# COMM.net
KiCad netlist of a schematic drawn in Altium Designer
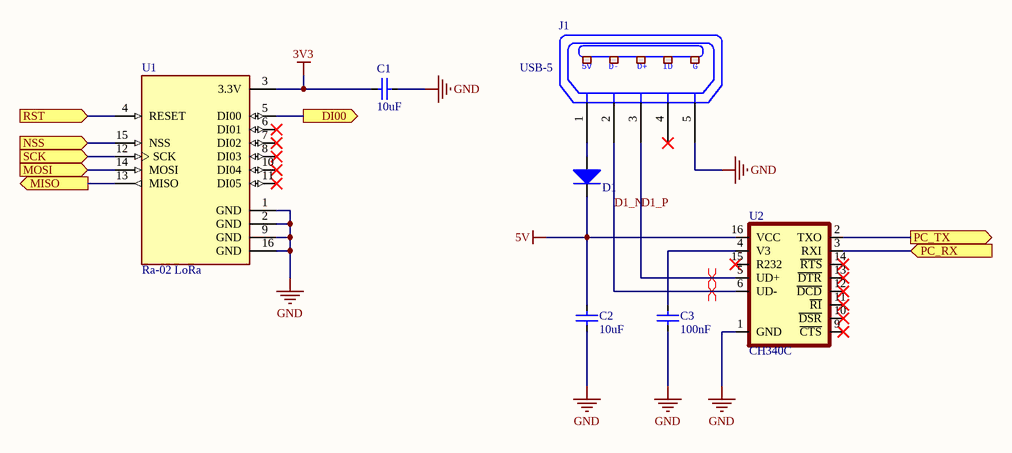
[diagram p0: COMM.SchDoc]

(export (version "E")
  (design (tool "Eeschema 10.0.6"))
  (components
    (comp (ref "C1")
      (value "10uF")
      (footprint "CAP_0805")
      (description "Capacitor")
      (fields (field (name "PUBLISHER") "Altium Limited"))
      (libsource (lib "My Library") (part "CapSMD"))
    )
    (comp (ref "C2")
      (value "10uF")
      (footprint "CAP_0805")
      (description "Capacitor")
      (fields (field (name "PUBLISHER") "Altium Limited"))
      (libsource (lib "My Library") (part "CapSMD"))
    )
    (comp (ref "C3")
      (value "100nF")
      (footprint "CAP_0805")
      (description "Capacitor")
      (fields (field (name "PUBLISHER") "Altium Limited"))
      (libsource (lib "My Library") (part "CapSMD"))
    )
    (comp (ref "D1")
      (value "Diode SMD")
      (footprint "DIO-214AC(SMA)")
      (description "Default Diode")
      (fields (field (name "PUBLISHER") "Altium Limited"))
      (libsource (lib "My Library") (part "Diode SMD"))
    )
    (comp (ref "J1")
      (value "USB-5")
      (footprint "USB-M1")
      (fields
        (field (name "MANUFACTURER") "FCI")
        (field (name "MANUFACTURER PART NUMBER") "10118193-0001LF")
        (field (name ".CREATOR") "MM")
        (field (name ".CHECKED PCB") "RF")
        (field (name ".CHECKED SCH") "MM")
      )
      (libsource (lib "My Library") (part "USB-5"))
    )
    (comp (ref "U1")
      (value "Ra-02 LoRa")
      (footprint "Ra-02")
      (description "LoRa Module Ra-02")
      (libsource (lib "My Library") (part "Ra-02 LoRa"))
    )
    (comp (ref "U2")
      (value "CH340C")
      (footprint "SOP-16")
      (description "USB to serial chip CH340")
      (fields (field (name "MF") "WCH"))
      (libsource (lib "My Library") (part "CH340C"))
    )
  )
  (nets
    (net (code "1") (name "/D1_N") (class "Default")
      (node (ref "J1") (pin "2") (pinfunction "P2_2") (pintype "passive"))
      (node (ref "U2") (pin "6") (pinfunction "UD-_6") (pintype "bidirectional"))
    )
    (net (code "2") (name "/D1_P") (class "Default")
      (node (ref "J1") (pin "3") (pinfunction "P3_3") (pintype "passive"))
      (node (ref "U2") (pin "5") (pinfunction "UD+_5") (pintype "bidirectional"))
    )
    (net (code "3") (name "/DI00") (class "Default")
      (node (ref "U1") (pin "5") (pinfunction "DI00_5") (pintype "bidirectional"))
    )
    (net (code "4") (name "/MISO") (class "Default")
      (node (ref "U1") (pin "13") (pinfunction "MISO_13") (pintype "output"))
    )
    (net (code "5") (name "/MOSI") (class "Default")
      (node (ref "U1") (pin "14") (pinfunction "MOSI_14") (pintype "input"))
    )
    (net (code "6") (name "/NSS") (class "Default")
      (node (ref "U1") (pin "15") (pinfunction "NSS_15") (pintype "input"))
    )
    (net (code "7") (name "/PC_RX") (class "Default")
      (node (ref "U2") (pin "3") (pinfunction "RXI_3") (pintype "bidirectional"))
    )
    (net (code "8") (name "/PC_TX") (class "Default")
      (node (ref "U2") (pin "2") (pinfunction "TXO_2") (pintype "bidirectional"))
    )
    (net (code "9") (name "/RST") (class "Default")
      (node (ref "U1") (pin "4") (pinfunction "RESET_4") (pintype "input"))
    )
    (net (code "10") (name "/SCK") (class "Default")
      (node (ref "U1") (pin "12") (pinfunction "SCK_12") (pintype "input"))
    )
    (net (code "11") (name "3V3") (class "Default")
      (node (ref "C1") (pin "2") (pinfunction "2_2") (pintype "passive"))
      (node (ref "U1") (pin "3") (pinfunction "3.3V_3") (pintype "power_in"))
    )
    (net (code "12") (name "5V") (class "Default")
      (node (ref "C2") (pin "2") (pinfunction "2_2") (pintype "passive"))
      (node (ref "D1") (pin "2") (pinfunction "K_2") (pintype "passive"))
      (node (ref "U2") (pin "16") (pinfunction "VCC_16") (pintype "bidirectional"))
    )
    (net (code "13") (name "GND") (class "Default")
      (node (ref "C1") (pin "1") (pinfunction "1_1") (pintype "passive"))
      (node (ref "C2") (pin "1") (pinfunction "1_1") (pintype "passive"))
      (node (ref "C3") (pin "1") (pinfunction "1_1") (pintype "passive"))
      (node (ref "J1") (pin "5") (pinfunction "P5_5") (pintype "passive"))
      (node (ref "U1") (pin "1") (pinfunction "GND_1") (pintype "power_in"))
      (node (ref "U1") (pin "16") (pinfunction "GND_16") (pintype "power_in"))
      (node (ref "U1") (pin "2") (pinfunction "GND_2") (pintype "power_in"))
      (node (ref "U1") (pin "9") (pinfunction "GND_9") (pintype "power_in"))
      (node (ref "U2") (pin "1") (pinfunction "GND_1") (pintype "bidirectional"))
    )
    (net (code "14") (name "Net-(D1-A)") (class "Default")
      (node (ref "D1") (pin "1") (pinfunction "A_1") (pintype "passive"))
      (node (ref "J1") (pin "1") (pinfunction "P1_1") (pintype "passive"))
    )
    (net (code "15") (name "Net-(U2-V3)") (class "Default")
      (node (ref "C3") (pin "2") (pinfunction "2_2") (pintype "passive"))
      (node (ref "U2") (pin "4") (pinfunction "V3_4") (pintype "bidirectional"))
    )
    (net (code "16") (name "unconnected-(J1-P4-Pad4)") (class "Default")
      (node (ref "J1") (pin "4") (pinfunction "P4_4") (pintype "passive+no_connect"))
    )
    (net (code "17") (name "unconnected-(U1-DI01-Pad6)") (class "Default")
      (node (ref "U1") (pin "6") (pinfunction "DI01_6") (pintype "bidirectional+no_connect"))
    )
    (net (code "18") (name "unconnected-(U1-DI02-Pad7)") (class "Default")
      (node (ref "U1") (pin "7") (pinfunction "DI02_7") (pintype "bidirectional+no_connect"))
    )
    (net (code "19") (name "unconnected-(U1-DI03-Pad8)") (class "Default")
      (node (ref "U1") (pin "8") (pinfunction "DI03_8") (pintype "bidirectional+no_connect"))
    )
    (net (code "20") (name "unconnected-(U1-DI04-Pad10)") (class "Default")
      (node (ref "U1") (pin "10") (pinfunction "DI04_10") (pintype "bidirectional+no_connect"))
    )
    (net (code "21") (name "unconnected-(U1-DI05-Pad11)") (class "Default")
      (node (ref "U1") (pin "11") (pinfunction "DI05_11") (pintype "bidirectional+no_connect"))
    )
    (net (code "22") (name "unconnected-(U2-R232-Pad15)") (class "Default")
      (node (ref "U2") (pin "15") (pinfunction "R232_15") (pintype "bidirectional+no_connect"))
    )
    (net (code "23") (name "unconnected-(U2-~{CTS}-Pad9)") (class "Default")
      (node (ref "U2") (pin "9") (pinfunction "~{CTS}_9") (pintype "bidirectional+no_connect"))
    )
    (net (code "24") (name "unconnected-(U2-~{DCD}-Pad12)") (class "Default")
      (node (ref "U2") (pin "12") (pinfunction "~{DCD}_12") (pintype "bidirectional+no_connect"))
    )
    (net (code "25") (name "unconnected-(U2-~{DSR}-Pad10)") (class "Default")
      (node (ref "U2") (pin "10") (pinfunction "~{DSR}_10") (pintype "bidirectional+no_connect"))
    )
    (net (code "26") (name "unconnected-(U2-~{DTR}-Pad13)") (class "Default")
      (node (ref "U2") (pin "13") (pinfunction "~{DTR}_13") (pintype "bidirectional+no_connect"))
    )
    (net (code "27") (name "unconnected-(U2-~{RI}-Pad11)") (class "Default")
      (node (ref "U2") (pin "11") (pinfunction "~{RI}_11") (pintype "bidirectional+no_connect"))
    )
    (net (code "28") (name "unconnected-(U2-~{RTS}-Pad14)") (class "Default")
      (node (ref "U2") (pin "14") (pinfunction "~{RTS}_14") (pintype "bidirectional+no_connect"))
    )
  )
)
